# EcobitNRF9160_EV3.net
KiCad netlist of a schematic drawn in EAGLE
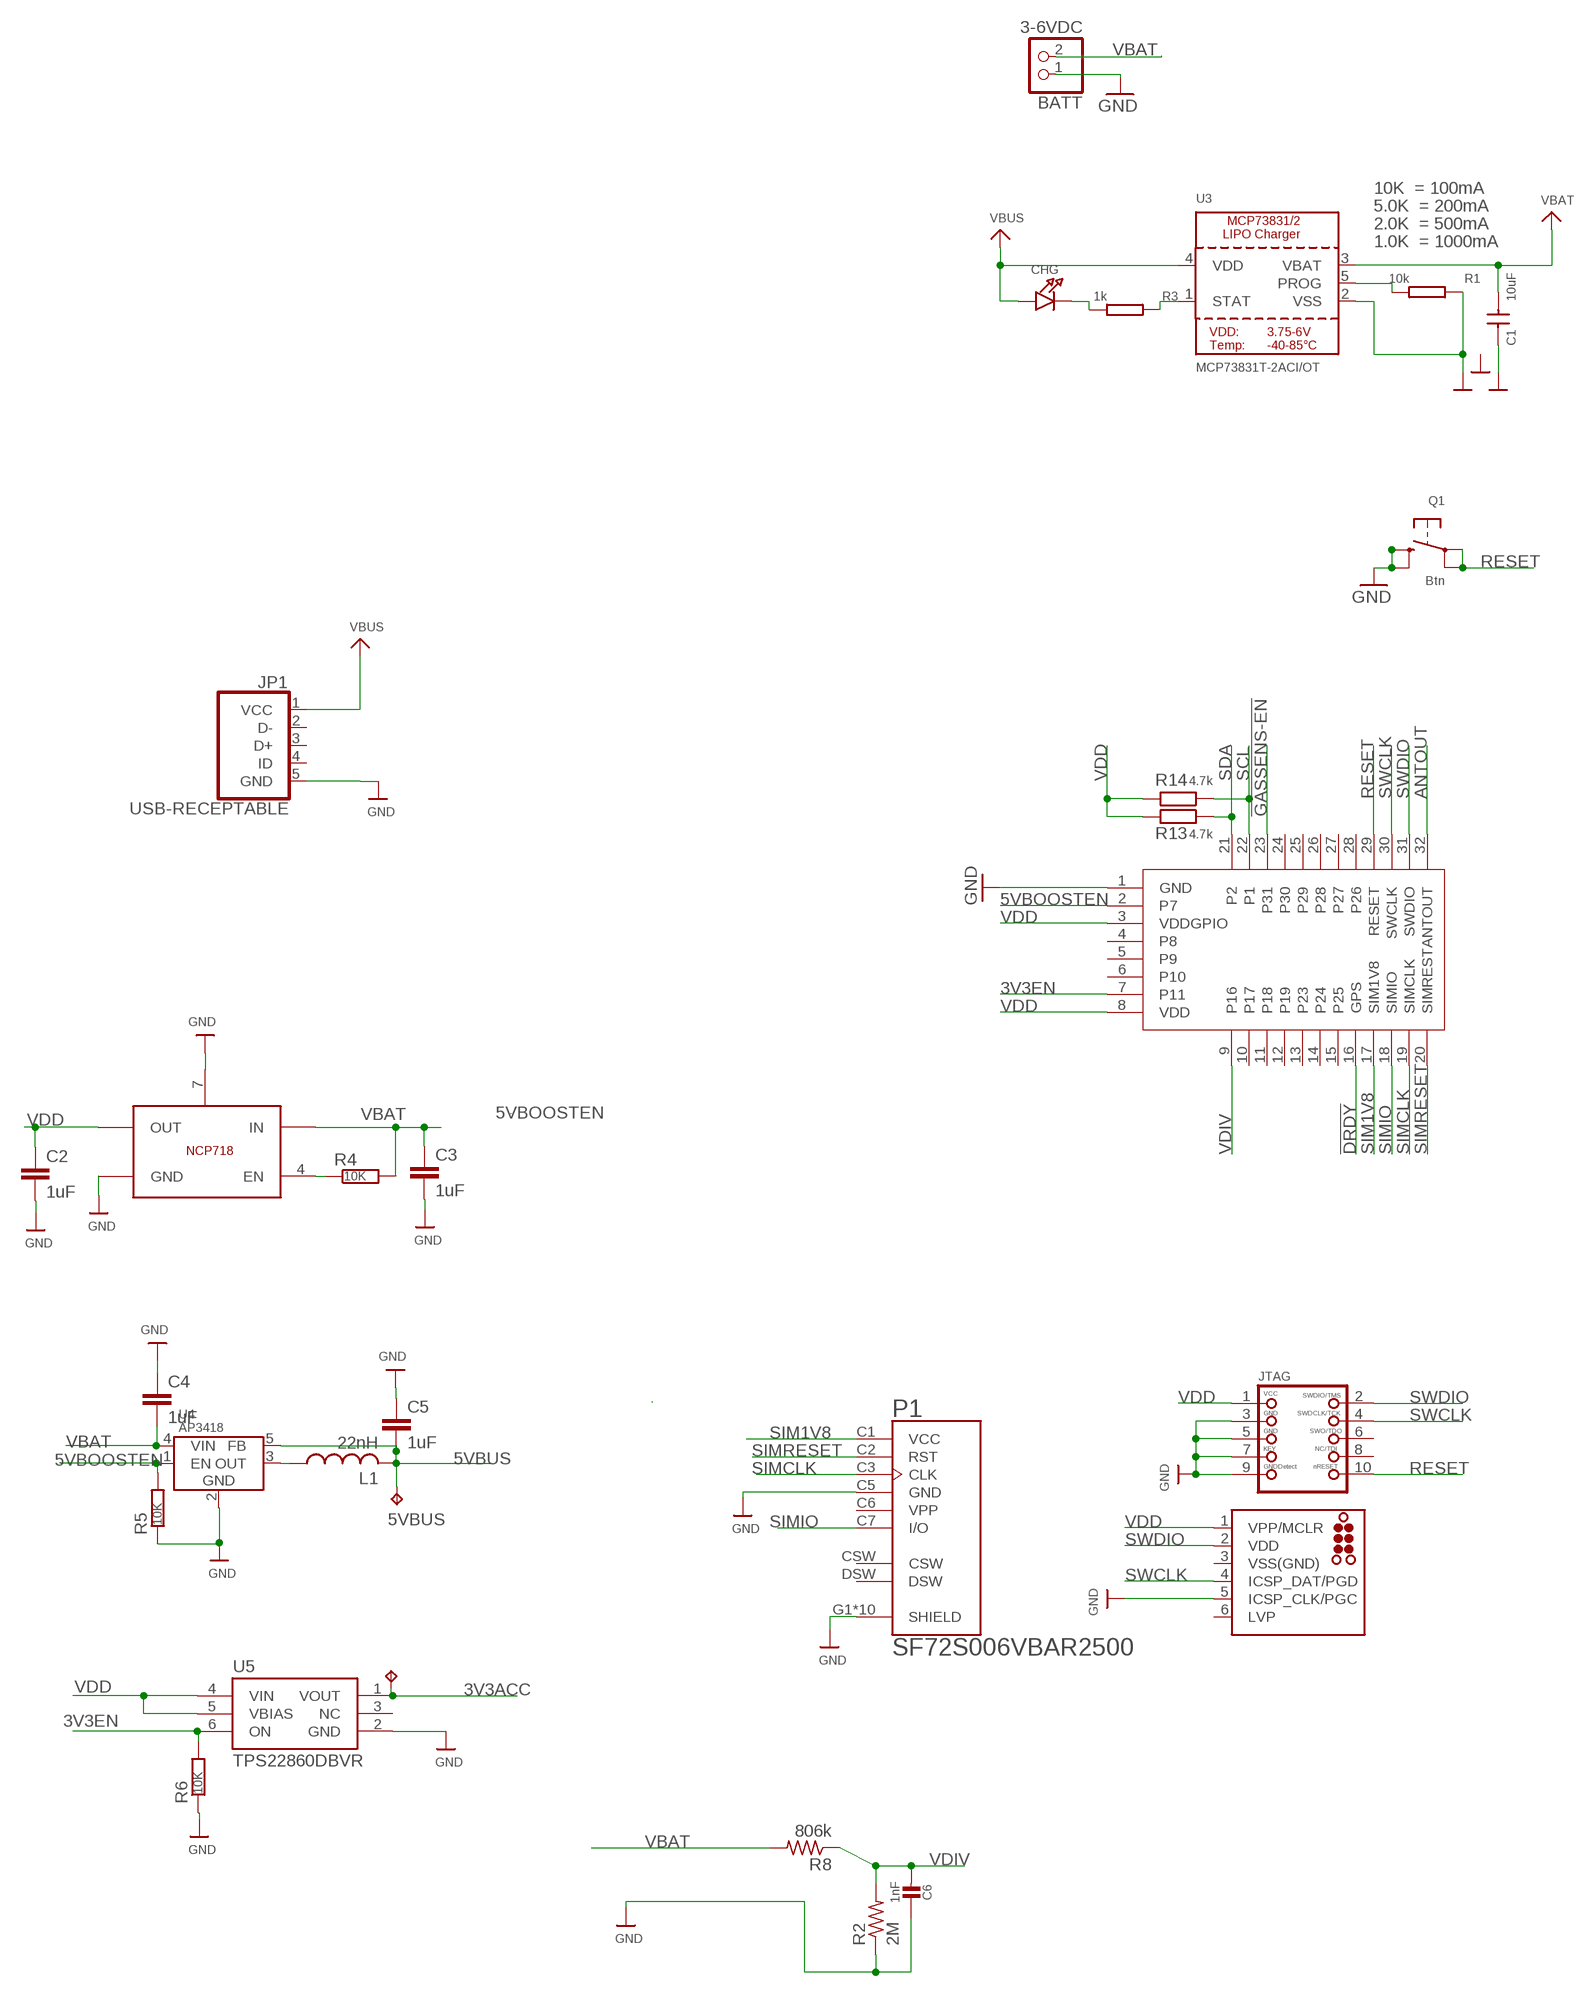
[diagram p0: schematic, sheet 1, part 1 of 2]
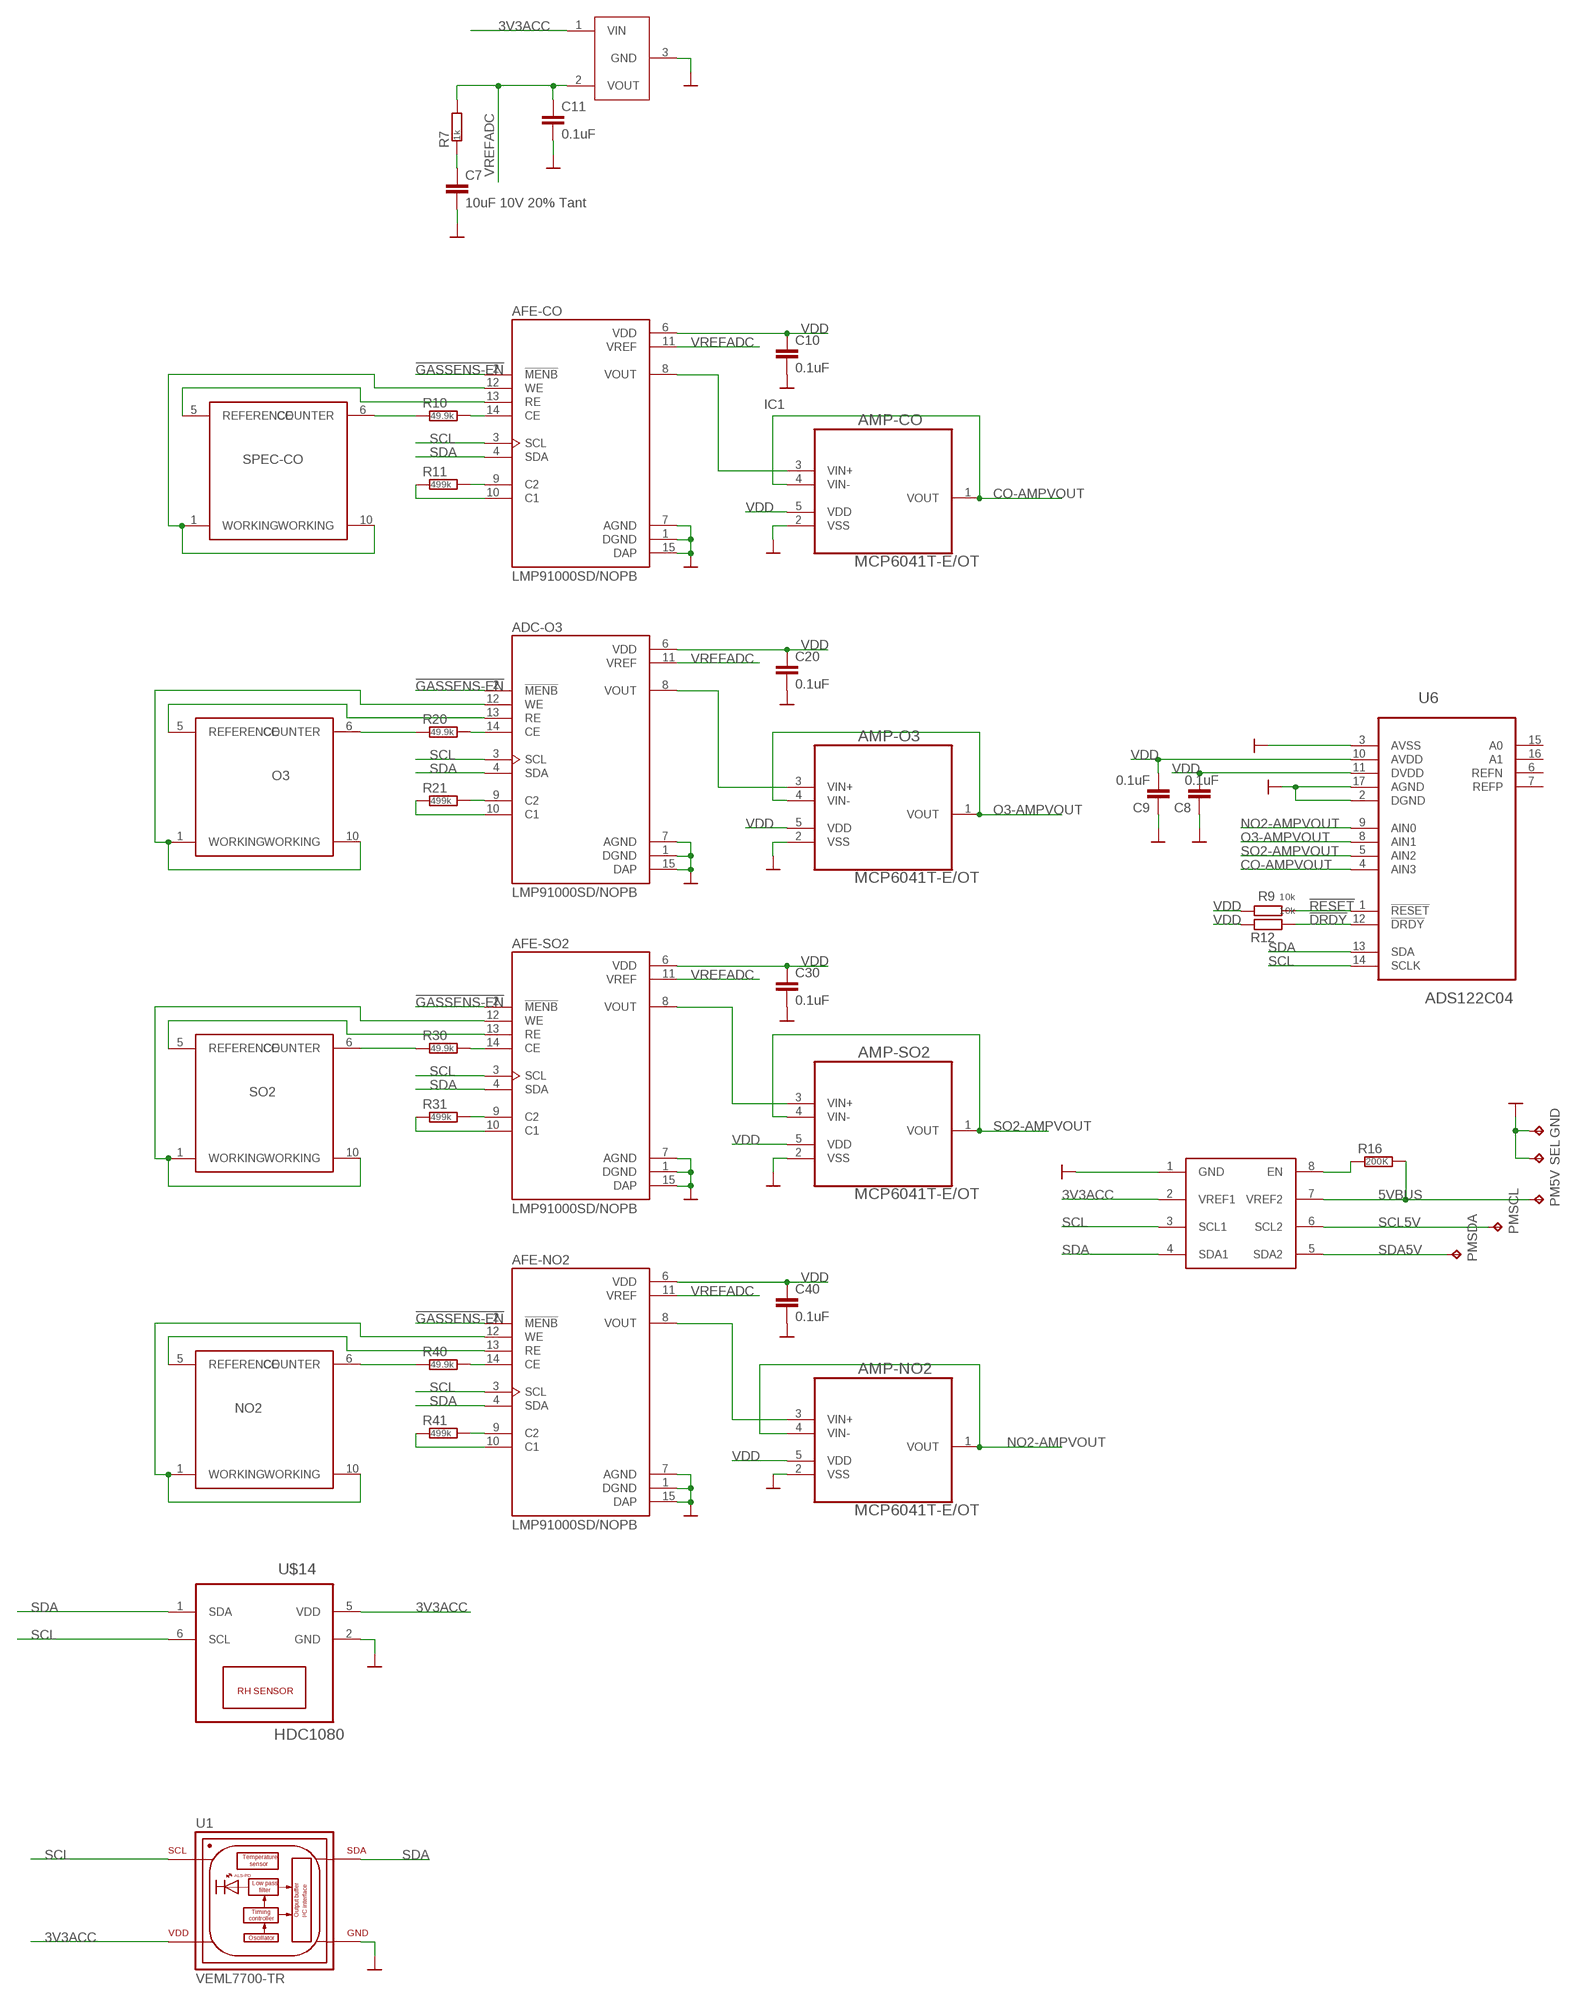
[diagram p1: schematic, sheet 1, part 2 of 2]

(export (version "E")
  (design (tool "Eeschema 10.0.6"))
  (components
    (comp (ref "5VBUS")
      (value "TPTP15R")
      (footprint "eagle-import:TP15R")
      (libsource (lib "eagle-import") (part "TPTP15R"))
    )
    (comp (ref "5VBUS1")
      (value "TPTP15R")
      (footprint "eagle-import:TP15R")
      (libsource (lib "eagle-import") (part "TPTP15R"))
    )
    (comp (ref "ADC-O3")
      (value "LMP91000SD/NOPB")
      (footprint "eagle-import:SON50P400X400X80-15N")
      (fields (field (name "MF") "Texas Instruments"))
      (libsource (lib "eagle-import") (part "LMP91000SD/NOPB"))
    )
    (comp (ref "AFE-CO")
      (value "LMP91000SD/NOPB")
      (footprint "eagle-import:SON50P400X400X80-15N")
      (fields (field (name "MF") "Texas Instruments"))
      (libsource (lib "eagle-import") (part "LMP91000SD/NOPB"))
    )
    (comp (ref "AFE-NO2")
      (value "LMP91000SD/NOPB")
      (footprint "eagle-import:SON50P400X400X80-15N")
      (fields (field (name "MF") "Texas Instruments"))
      (libsource (lib "eagle-import") (part "LMP91000SD/NOPB"))
    )
    (comp (ref "AFE-SO2")
      (value "LMP91000SD/NOPB")
      (footprint "eagle-import:SON50P400X400X80-15N")
      (fields (field (name "MF") "Texas Instruments"))
      (libsource (lib "eagle-import") (part "LMP91000SD/NOPB"))
    )
    (comp (ref "AMP-CO")
      (value "MCP6041T-E/OT")
      (footprint "eagle-import:SOT95P320X145-5N")
      (fields (field (name "MF") "Microchip"))
      (libsource (lib "eagle-import") (part "MCP6041T-E/OT"))
    )
    (comp (ref "AMP-NO2")
      (value "MCP6041T-E/OT")
      (footprint "eagle-import:SOT95P320X145-5N")
      (fields (field (name "MF") "Microchip"))
      (libsource (lib "eagle-import") (part "MCP6041T-E/OT"))
    )
    (comp (ref "AMP-O3")
      (value "MCP6041T-E/OT")
      (footprint "eagle-import:SOT95P320X145-5N")
      (fields (field (name "MF") "Microchip"))
      (libsource (lib "eagle-import") (part "MCP6041T-E/OT"))
    )
    (comp (ref "AMP-SO2")
      (value "MCP6041T-E/OT")
      (footprint "eagle-import:SOT95P320X145-5N")
      (fields (field (name "MF") "Microchip"))
      (libsource (lib "eagle-import") (part "MCP6041T-E/OT"))
    )
    (comp (ref "BATT")
      (value "3-6VDC")
      (footprint "eagle-import:JSTPH2")
      (libsource (lib "eagle-import") (part "CON_JST_PH_2PIN"))
    )
    (comp (ref "C1")
      (value "10uF")
      (footprint "eagle-import:C-0402")
      (libsource (lib "eagle-import") (part "CAP0402"))
    )
    (comp (ref "C2")
      (value "1uF")
      (footprint "eagle-import:RESC0402_N")
      (libsource (lib "eagle-import") (part "CAPACITOR_0402_N"))
    )
    (comp (ref "C3")
      (value "1uF")
      (footprint "eagle-import:RESC0402_N")
      (libsource (lib "eagle-import") (part "CAPACITOR_0402_N"))
    )
    (comp (ref "C4")
      (value "1uF")
      (footprint "eagle-import:RESC0402_N")
      (libsource (lib "eagle-import") (part "CAPACITOR_0402_N"))
    )
    (comp (ref "C5")
      (value "1uF")
      (footprint "eagle-import:RESC0402_N")
      (libsource (lib "eagle-import") (part "CAPACITOR_0402_N"))
    )
    (comp (ref "C6")
      (value "1nF")
      (footprint "eagle-import:0603-NO")
      (libsource (lib "eagle-import") (part "CAP_CERAMIC0603_NO"))
    )
    (comp (ref "C7")
      (value "10uF 10V 20% Tant")
      (footprint "eagle-import:RESC0805_N")
      (libsource (lib "eagle-import") (part "CAPACITOR_0805_N"))
    )
    (comp (ref "C8")
      (value "0.1uF")
      (footprint "eagle-import:RESC0603_N")
      (libsource (lib "eagle-import") (part "CAPACITOR_0603_N"))
    )
    (comp (ref "C9")
      (value "0.1uF")
      (footprint "eagle-import:RESC0603_N")
      (libsource (lib "eagle-import") (part "CAPACITOR_0603_N"))
    )
    (comp (ref "C10")
      (value "0.1uF")
      (footprint "eagle-import:RESC0603_N")
      (libsource (lib "eagle-import") (part "CAPACITOR_0603_N"))
    )
    (comp (ref "C11")
      (value "0.1uF")
      (footprint "eagle-import:RESC0603_N")
      (libsource (lib "eagle-import") (part "CAPACITOR_0603_N"))
    )
    (comp (ref "C20")
      (value "0.1uF")
      (footprint "eagle-import:RESC0603_N")
      (libsource (lib "eagle-import") (part "CAPACITOR_0603_N"))
    )
    (comp (ref "C30")
      (value "0.1uF")
      (footprint "eagle-import:RESC0603_N")
      (libsource (lib "eagle-import") (part "CAPACITOR_0603_N"))
    )
    (comp (ref "C40")
      (value "0.1uF")
      (footprint "eagle-import:RESC0603_N")
      (libsource (lib "eagle-import") (part "CAPACITOR_0603_N"))
    )
    (comp (ref "CHG")
      (value "LED0805_NOOUTLINE")
      (footprint "eagle-import:CHIPLED_0805_NOOUTLINE")
      (libsource (lib "eagle-import") (part "LED0805_NOOUTLINE"))
    )
    (comp (ref "GND")
      (value "TPTP15R")
      (footprint "eagle-import:TP15R")
      (libsource (lib "eagle-import") (part "TPTP15R"))
    )
    (comp (ref "IC1")
      (value "ISL60002DIH320Z-TK")
      (footprint "eagle-import:SOT-23-3")
      (libsource (lib "eagle-import") (part "ISL60002DIH320Z-TK"))
    )
    (comp (ref "J2")
      (value "TC2030-MCP-NL")
      (footprint "eagle-import:TC2030-MCP-NL")
      (libsource (lib "eagle-import") (part "TC2030-MCP-NL"))
    )
    (comp (ref "JP1")
      (value "USB-RECEPTABLE")
      (footprint "eagle-import:FCI-10103594-0001LF")
      (libsource (lib "eagle-import") (part "USB-RECEPTABLE"))
    )
    (comp (ref "JTAG")
      (value "JTAG-CORTEXM3")
      (footprint "eagle-import:2X05_1.27MM_SMT")
      (libsource (lib "eagle-import") (part "JTAG-CORTEXM3"))
    )
    (comp (ref "L1")
      (value "22nH")
      (footprint "eagle-import:RESC0603_N")
      (libsource (lib "eagle-import") (part "INDUCTOR_0603_N"))
    )
    (comp (ref "P1")
      (value "SF72S006VBAR2500")
      (footprint "eagle-import:JAE_SF72S006VBAR2500")
      (fields (field (name "MF") "JAE Electronics"))
      (libsource (lib "eagle-import") (part "SF72S006VBAR2500"))
    )
    (comp (ref "PM5V")
      (value "TPTP15R")
      (footprint "eagle-import:TP15R")
      (libsource (lib "eagle-import") (part "TPTP15R"))
    )
    (comp (ref "PMSCL")
      (value "TPTP15R")
      (footprint "eagle-import:TP15R")
      (libsource (lib "eagle-import") (part "TPTP15R"))
    )
    (comp (ref "PMSDA")
      (value "TPTP15R")
      (footprint "eagle-import:TP15R")
      (libsource (lib "eagle-import") (part "TPTP15R"))
    )
    (comp (ref "Q1")
      (value "Btn")
      (footprint "eagle-import:BTN_KMR2_4.6X2.8")
      (libsource (lib "eagle-import") (part "SWITCH_TACT_SMT4.6X2.8"))
    )
    (comp (ref "R1")
      (value "10k")
      (footprint "eagle-import:R0402")
      (libsource (lib "eagle-import") (part "RESR0402"))
    )
    (comp (ref "R2")
      (value "2M")
      (footprint "eagle-import:R0603")
      (libsource (lib "eagle-import") (part "R-US_R0603"))
    )
    (comp (ref "R3")
      (value "1k")
      (footprint "eagle-import:R0402")
      (libsource (lib "eagle-import") (part "RESR0402"))
    )
    (comp (ref "R4")
      (value "10K")
      (footprint "eagle-import:RESC0402_N")
      (libsource (lib "eagle-import") (part "RESISTOR_0402_N"))
    )
    (comp (ref "R5")
      (value "10K")
      (footprint "eagle-import:RESC0402_N")
      (libsource (lib "eagle-import") (part "RESISTOR_0402_N"))
    )
    (comp (ref "R6")
      (value "10K")
      (footprint "eagle-import:RESC0402_N")
      (libsource (lib "eagle-import") (part "RESISTOR_0402_N"))
    )
    (comp (ref "R7")
      (value "1k")
      (footprint "eagle-import:RESC0603_N")
      (libsource (lib "eagle-import") (part "RESISTOR_0603_N"))
    )
    (comp (ref "R8")
      (value "806k")
      (footprint "eagle-import:R0603")
      (libsource (lib "eagle-import") (part "R-US_R0603"))
    )
    (comp (ref "R9")
      (value "10k")
      (footprint "eagle-import:RESC0603_N")
      (libsource (lib "eagle-import") (part "RESISTOR_0603_N"))
    )
    (comp (ref "R10")
      (value "49.9k")
      (footprint "eagle-import:RESC0603_N")
      (libsource (lib "eagle-import") (part "RESISTOR_0603_N"))
    )
    (comp (ref "R11")
      (value "499k")
      (footprint "eagle-import:RESC0603_N")
      (libsource (lib "eagle-import") (part "RESISTOR_0603_N"))
    )
    (comp (ref "R12")
      (value "10k")
      (footprint "eagle-import:RESC0603_N")
      (libsource (lib "eagle-import") (part "RESISTOR_0603_N"))
    )
    (comp (ref "R13")
      (value "4.7k")
      (footprint "eagle-import:RESC0603_N")
      (libsource (lib "eagle-import") (part "RESISTOR_0603_N"))
    )
    (comp (ref "R14")
      (value "4.7k")
      (footprint "eagle-import:RESC0603_N")
      (libsource (lib "eagle-import") (part "RESISTOR_0603_N"))
    )
    (comp (ref "R16")
      (value "200K")
      (footprint "eagle-import:RESC0402_N")
      (libsource (lib "eagle-import") (part "RESISTOR_0402_N"))
    )
    (comp (ref "R20")
      (value "49.9k")
      (footprint "eagle-import:RESC0603_N")
      (libsource (lib "eagle-import") (part "RESISTOR_0603_N"))
    )
    (comp (ref "R21")
      (value "499k")
      (footprint "eagle-import:RESC0603_N")
      (libsource (lib "eagle-import") (part "RESISTOR_0603_N"))
    )
    (comp (ref "R30")
      (value "49.9k")
      (footprint "eagle-import:RESC0603_N")
      (libsource (lib "eagle-import") (part "RESISTOR_0603_N"))
    )
    (comp (ref "R31")
      (value "499k")
      (footprint "eagle-import:RESC0603_N")
      (libsource (lib "eagle-import") (part "RESISTOR_0603_N"))
    )
    (comp (ref "R40")
      (value "49.9k")
      (footprint "eagle-import:RESC0603_N")
      (libsource (lib "eagle-import") (part "RESISTOR_0603_N"))
    )
    (comp (ref "R41")
      (value "499k")
      (footprint "eagle-import:RESC0603_N")
      (libsource (lib "eagle-import") (part "RESISTOR_0603_N"))
    )
    (comp (ref "SEL")
      (value "TPTP15R")
      (footprint "eagle-import:TP15R")
      (libsource (lib "eagle-import") (part "TPTP15R"))
    )
    (comp (ref "SENS-CO")
      (value "SPECSENSOR")
      (footprint "eagle-import:SPECSENSOR")
      (libsource (lib "eagle-import") (part "SPECSENSOR"))
    )
    (comp (ref "SENS-NO2")
      (value "SPECSENSOR")
      (footprint "eagle-import:SPECSENSOR")
      (libsource (lib "eagle-import") (part "SPECSENSOR"))
    )
    (comp (ref "SENS-O3")
      (value "SPECSENSOR")
      (footprint "eagle-import:SPECSENSOR")
      (libsource (lib "eagle-import") (part "SPECSENSOR"))
    )
    (comp (ref "SENS-SO2")
      (value "SPECSENSOR")
      (footprint "eagle-import:SPECSENSOR")
      (libsource (lib "eagle-import") (part "SPECSENSOR"))
    )
    (comp (ref "U$14")
      (value "HDC1080")
      (footprint "eagle-import:TI-S-PWSON-N6")
      (libsource (lib "eagle-import") (part "HDC1080"))
    )
    (comp (ref "U$35")
      (value "NRF9160MODULE")
      (footprint "eagle-import:NRF9160CASTALLATEDMODULE")
      (libsource (lib "eagle-import") (part "NRF9160MODULE"))
    )
    (comp (ref "U1")
      (value "VEML7700-TR")
      (footprint "eagle-import:XDCR_VEML7700-TR")
      (fields (field (name "DIGI-KEY_PART_NUMBER") "VEML7700CT-ND") (field (name "MF") "Vishay"))
      (libsource (lib "eagle-import") (part "VEML7700-TR"))
    )
    (comp (ref "U2")
      (value "NCP718")
      (footprint "eagle-import:NCP718-WDFN6")
      (libsource (lib "eagle-import") (part "NCP718"))
    )
    (comp (ref "U3")
      (value "MCP73831T-2ACI/OT")
      (footprint "eagle-import:SOT23-5")
      (libsource (lib "eagle-import") (part "MCP73831/2"))
    )
    (comp (ref "U4")
      (value "AP3418")
      (footprint "eagle-import:SOT25")
      (libsource (lib "eagle-import") (part "AP3418"))
    )
    (comp (ref "U5")
      (value "TPS22860DBVR")
      (footprint "eagle-import:R-PDSO-G6")
      (libsource (lib "eagle-import") (part "TPS22860DBVR"))
    )
    (comp (ref "U6")
      (value "ADS122C04")
      (footprint "eagle-import:QFN50P300X300X80-16N")
      (fields (field (name "MF") "Texas Instruments") (field (name "MP") "ADS7924IRTER"))
      (libsource (lib "eagle-import") (part "ADS122C04"))
    )
    (comp (ref "U7")
      (value "PCA9306")
      (footprint "eagle-import:PSON35P135X100X50-8N")
      (libsource (lib "eagle-import") (part "PCA9306"))
    )
  )
  (nets
    (net (code "1") (name "/3V3ACC") (class "Default")
      (node (ref "5VBUS1") (pin "TP") (pinfunction "TP_TP") (pintype "input"))
      (node (ref "IC1") (pin "1") (pinfunction "VIN_1") (pintype "power_in"))
      (node (ref "U$14") (pin "5") (pinfunction "VDD_5") (pintype "output"))
      (node (ref "U1") (pin "2") (pinfunction "VDD_2") (pintype "power_in"))
      (node (ref "U5") (pin "1") (pinfunction "VOUT_1") (pintype "power_in"))
      (node (ref "U7") (pin "2") (pinfunction "VREF1_2") (pintype "bidirectional"))
    )
    (net (code "2") (name "/3V3EN") (class "Default")
      (node (ref "R6") (pin "2") (pinfunction "2_2") (pintype "passive"))
      (node (ref "U$35") (pin "7") (pinfunction "P11_7") (pintype "bidirectional"))
      (node (ref "U5") (pin "6") (pinfunction "ON_6") (pintype "input"))
    )
    (net (code "3") (name "/5VBOOSTEN") (class "Default")
      (node (ref "R5") (pin "2") (pinfunction "2_2") (pintype "passive"))
      (node (ref "U$35") (pin "2") (pinfunction "P7_2") (pintype "bidirectional"))
      (node (ref "U4") (pin "1") (pinfunction "EN_1") (pintype "bidirectional"))
    )
    (net (code "4") (name "/5VBUS") (class "Default")
      (node (ref "5VBUS") (pin "TP") (pinfunction "TP_TP") (pintype "input"))
      (node (ref "C5") (pin "2") (pinfunction "2_2") (pintype "passive"))
      (node (ref "L1") (pin "2") (pinfunction "2_2") (pintype "passive"))
      (node (ref "PM5V") (pin "TP") (pinfunction "TP_TP") (pintype "input"))
      (node (ref "R16") (pin "2") (pinfunction "2_2") (pintype "passive"))
      (node (ref "U4") (pin "5") (pinfunction "FB_5") (pintype "bidirectional"))
      (node (ref "U7") (pin "7") (pinfunction "VREF2_7") (pintype "bidirectional"))
    )
    (net (code "5") (name "/ANTOUT") (class "Default")
      (node (ref "U$35") (pin "32") (pinfunction "ANTOUT_32") (pintype "bidirectional"))
    )
    (net (code "6") (name "/CO-AMPVOUT") (class "Default")
      (node (ref "AMP-CO") (pin "1") (pinfunction "VOUT_1") (pintype "output"))
      (node (ref "AMP-CO") (pin "4") (pinfunction "VIN-_4") (pintype "input"))
      (node (ref "U6") (pin "4") (pinfunction "AIN3_4") (pintype "input"))
    )
    (net (code "9") (name "/NO2-AMPVOUT") (class "Default")
      (node (ref "AMP-NO2") (pin "1") (pinfunction "VOUT_1") (pintype "output"))
      (node (ref "AMP-NO2") (pin "4") (pinfunction "VIN-_4") (pintype "input"))
      (node (ref "U6") (pin "9") (pinfunction "AIN0_9") (pintype "input"))
    )
    (net (code "11") (name "/O3-AMPVOUT") (class "Default")
      (node (ref "AMP-O3") (pin "1") (pinfunction "VOUT_1") (pintype "output"))
      (node (ref "AMP-O3") (pin "4") (pinfunction "VIN-_4") (pintype "input"))
      (node (ref "U6") (pin "8") (pinfunction "AIN1_8") (pintype "input"))
    )
    (net (code "12") (name "/RESET") (class "Default")
      (node (ref "JTAG") (pin "10") (pinfunction "10_10") (pintype "passive"))
      (node (ref "Q1") (pin "A") (pinfunction "P_A") (pintype "passive"))
      (node (ref "Q1") (pin "A'") (pinfunction "P1_A'") (pintype "passive"))
      (node (ref "U$35") (pin "29") (pinfunction "RESET_29") (pintype "bidirectional"))
    )
    (net (code "13") (name "/SCL") (class "Default")
      (node (ref "ADC-O3") (pin "3") (pinfunction "SCL_3") (pintype "input"))
      (node (ref "AFE-CO") (pin "3") (pinfunction "SCL_3") (pintype "input"))
      (node (ref "AFE-NO2") (pin "3") (pinfunction "SCL_3") (pintype "input"))
      (node (ref "AFE-SO2") (pin "3") (pinfunction "SCL_3") (pintype "input"))
      (node (ref "R14") (pin "1") (pinfunction "1_1") (pintype "passive"))
      (node (ref "U$14") (pin "6") (pinfunction "SCL_6") (pintype "passive"))
      (node (ref "U$35") (pin "22") (pinfunction "P1_22") (pintype "bidirectional"))
      (node (ref "U1") (pin "1") (pinfunction "SCL_1") (pintype "input"))
      (node (ref "U6") (pin "14") (pinfunction "SCLK_14") (pintype "input"))
      (node (ref "U7") (pin "3") (pinfunction "SCL1_3") (pintype "bidirectional"))
    )
    (net (code "14") (name "/SCL5V") (class "Default")
      (node (ref "PMSCL") (pin "TP") (pinfunction "TP_TP") (pintype "input"))
      (node (ref "U7") (pin "6") (pinfunction "SCL2_6") (pintype "bidirectional"))
    )
    (net (code "15") (name "/SDA") (class "Default")
      (node (ref "ADC-O3") (pin "4") (pinfunction "SDA_4") (pintype "bidirectional"))
      (node (ref "AFE-CO") (pin "4") (pinfunction "SDA_4") (pintype "bidirectional"))
      (node (ref "AFE-NO2") (pin "4") (pinfunction "SDA_4") (pintype "bidirectional"))
      (node (ref "AFE-SO2") (pin "4") (pinfunction "SDA_4") (pintype "bidirectional"))
      (node (ref "R13") (pin "1") (pinfunction "1_1") (pintype "passive"))
      (node (ref "U$14") (pin "1") (pinfunction "SDA_1") (pintype "power_in"))
      (node (ref "U$35") (pin "21") (pinfunction "P2_21") (pintype "bidirectional"))
      (node (ref "U1") (pin "4") (pinfunction "SDA_4") (pintype "bidirectional"))
      (node (ref "U6") (pin "13") (pinfunction "SDA_13") (pintype "input"))
      (node (ref "U7") (pin "4") (pinfunction "SDA1_4") (pintype "bidirectional"))
    )
    (net (code "16") (name "/SDA5V") (class "Default")
      (node (ref "PMSDA") (pin "TP") (pinfunction "TP_TP") (pintype "input"))
      (node (ref "U7") (pin "5") (pinfunction "SDA2_5") (pintype "bidirectional"))
    )
    (net (code "17") (name "/SIM1V8") (class "Default")
      (node (ref "P1") (pin "C1") (pinfunction "VCC_C1") (pintype "power_in"))
      (node (ref "U$35") (pin "17") (pinfunction "SIM1V8_17") (pintype "bidirectional"))
    )
    (net (code "18") (name "/SIMCLK") (class "Default")
      (node (ref "P1") (pin "C3") (pinfunction "CLK_C3") (pintype "bidirectional"))
      (node (ref "U$35") (pin "19") (pinfunction "SIMCLK_19") (pintype "bidirectional"))
    )
    (net (code "19") (name "/SIMIO") (class "Default")
      (node (ref "P1") (pin "C7") (pinfunction "I/O_C7") (pintype "bidirectional"))
      (node (ref "U$35") (pin "18") (pinfunction "SIMIO_18") (pintype "bidirectional"))
    )
    (net (code "20") (name "/SIMRESET") (class "Default")
      (node (ref "P1") (pin "C2") (pinfunction "RST_C2") (pintype "bidirectional"))
      (node (ref "U$35") (pin "20") (pinfunction "SIMREST_20") (pintype "bidirectional"))
    )
    (net (code "22") (name "/SO2-AMPVOUT") (class "Default")
      (node (ref "AMP-SO2") (pin "1") (pinfunction "VOUT_1") (pintype "output"))
      (node (ref "AMP-SO2") (pin "4") (pinfunction "VIN-_4") (pintype "input"))
      (node (ref "U6") (pin "5") (pinfunction "AIN2_5") (pintype "input"))
    )
    (net (code "24") (name "/SWCLK") (class "Default")
      (node (ref "J2") (pin "4") (pinfunction "ICSP_DAT/PGD_4") (pintype "bidirectional"))
      (node (ref "JTAG") (pin "4") (pinfunction "4_4") (pintype "passive"))
      (node (ref "U$35") (pin "30") (pinfunction "SWCLK_30") (pintype "bidirectional"))
    )
    (net (code "25") (name "/SWDIO") (class "Default")
      (node (ref "J2") (pin "2") (pinfunction "VDD_2") (pintype "power_in"))
      (node (ref "JTAG") (pin "2") (pinfunction "2_2") (pintype "passive"))
      (node (ref "U$35") (pin "31") (pinfunction "SWDIO_31") (pintype "bidirectional"))
    )
    (net (code "26") (name "/VDD") (class "Default")
      (node (ref "ADC-O3") (pin "6") (pinfunction "VDD_6") (pintype "power_in"))
      (node (ref "AFE-CO") (pin "6") (pinfunction "VDD_6") (pintype "power_in"))
      (node (ref "AFE-NO2") (pin "6") (pinfunction "VDD_6") (pintype "power_in"))
      (node (ref "AFE-SO2") (pin "6") (pinfunction "VDD_6") (pintype "power_in"))
      (node (ref "AMP-CO") (pin "5") (pinfunction "VDD_5") (pintype "power_in"))
      (node (ref "AMP-NO2") (pin "5") (pinfunction "VDD_5") (pintype "power_in"))
      (node (ref "AMP-O3") (pin "5") (pinfunction "VDD_5") (pintype "power_in"))
      (node (ref "AMP-SO2") (pin "5") (pinfunction "VDD_5") (pintype "power_in"))
      (node (ref "C10") (pin "1") (pinfunction "1_1") (pintype "passive"))
      (node (ref "C2") (pin "1") (pinfunction "1_1") (pintype "passive"))
      (node (ref "C20") (pin "1") (pinfunction "1_1") (pintype "passive"))
      (node (ref "C30") (pin "1") (pinfunction "1_1") (pintype "passive"))
      (node (ref "C40") (pin "1") (pinfunction "1_1") (pintype "passive"))
      (node (ref "C8") (pin "2") (pinfunction "2_2") (pintype "passive"))
      (node (ref "C9") (pin "2") (pinfunction "2_2") (pintype "passive"))
      (node (ref "J2") (pin "1") (pinfunction "VPP/MCLR_1") (pintype "passive"))
      (node (ref "JTAG") (pin "1") (pinfunction "1_1") (pintype "passive"))
      (node (ref "R12") (pin "2") (pinfunction "2_2") (pintype "passive"))
      (node (ref "R13") (pin "2") (pinfunction "2_2") (pintype "passive"))
      (node (ref "R14") (pin "2") (pinfunction "2_2") (pintype "passive"))
      (node (ref "R9") (pin "2") (pinfunction "2_2") (pintype "passive"))
      (node (ref "U$35") (pin "3") (pinfunction "VDDGPIO_3") (pintype "bidirectional"))
      (node (ref "U$35") (pin "8") (pinfunction "VDD_8") (pintype "bidirectional"))
      (node (ref "U2") (pin "1") (pinfunction "OUT_1") (pintype "power_in"))
      (node (ref "U5") (pin "4") (pinfunction "VIN_4") (pintype "power_in"))
      (node (ref "U5") (pin "5") (pinfunction "VBIAS_5") (pintype "power_in"))
      (node (ref "U6") (pin "10") (pinfunction "AVDD_10") (pintype "input"))
      (node (ref "U6") (pin "11") (pinfunction "DVDD_11") (pintype "power_in"))
    )
    (net (code "27") (name "/VDIV") (class "Default")
      (node (ref "C6") (pin "2") (pinfunction "2_2") (pintype "passive"))
      (node (ref "R2") (pin "2") (pinfunction "2_2") (pintype "passive"))
      (node (ref "R8") (pin "1") (pinfunction "1_1") (pintype "passive"))
      (node (ref "U$35") (pin "9") (pinfunction "P16_9") (pintype "bidirectional"))
    )
    (net (code "28") (name "/VPP") (class "Default")
      (node (ref "P1") (pin "C6") (pinfunction "VPP_C6") (pintype "power_in"))
    )
    (net (code "29") (name "/VREFADC") (class "Default")
      (node (ref "ADC-O3") (pin "11") (pinfunction "VREF_11") (pintype "power_in"))
      (node (ref "AFE-CO") (pin "11") (pinfunction "VREF_11") (pintype "power_in"))
      (node (ref "AFE-NO2") (pin "11") (pinfunction "VREF_11") (pintype "power_in"))
      (node (ref "AFE-SO2") (pin "11") (pinfunction "VREF_11") (pintype "power_in"))
      (node (ref "C11") (pin "1") (pinfunction "1_1") (pintype "passive"))
      (node (ref "IC1") (pin "2") (pinfunction "VOUT_2") (pintype "power_in"))
      (node (ref "R7") (pin "2") (pinfunction "2_2") (pintype "passive"))
    )
    (net (code "30") (name "/VSS(GND)") (class "Default")
      (node (ref "J2") (pin "3") (pinfunction "VSS(GND)_3") (pintype "power_in"))
    )
    (net (code "31") (name "/~{DRDY}") (class "Default")
      (node (ref "R12") (pin "1") (pinfunction "1_1") (pintype "passive"))
      (node (ref "U$35") (pin "16") (pinfunction "GPS_16") (pintype "bidirectional"))
      (node (ref "U6") (pin "12") (pinfunction "~{DRDY}_12") (pintype "passive"))
    )
    (net (code "32") (name "/~{GASSENS-EN}") (class "Default")
      (node (ref "ADC-O3") (pin "2") (pinfunction "~{MENB}_2") (pintype "input"))
      (node (ref "AFE-CO") (pin "2") (pinfunction "~{MENB}_2") (pintype "input"))
      (node (ref "AFE-NO2") (pin "2") (pinfunction "~{MENB}_2") (pintype "input"))
      (node (ref "AFE-SO2") (pin "2") (pinfunction "~{MENB}_2") (pintype "input"))
      (node (ref "U$35") (pin "23") (pinfunction "P31_23") (pintype "bidirectional"))
    )
    (net (code "33") (name "/~{RESET}") (class "Default")
      (node (ref "R9") (pin "1") (pinfunction "1_1") (pintype "passive"))
      (node (ref "U6") (pin "1") (pinfunction "~{RESET}_1") (pintype "input"))
    )
    (net (code "34") (name "GND") (class "Default")
      (node (ref "ADC-O3") (pin "1") (pinfunction "DGND_1") (pintype "power_in"))
      (node (ref "ADC-O3") (pin "15") (pinfunction "DAP_15") (pintype "power_in"))
      (node (ref "ADC-O3") (pin "7") (pinfunction "AGND_7") (pintype "power_in"))
      (node (ref "AFE-CO") (pin "1") (pinfunction "DGND_1") (pintype "power_in"))
      (node (ref "AFE-CO") (pin "15") (pinfunction "DAP_15") (pintype "power_in"))
      (node (ref "AFE-CO") (pin "7") (pinfunction "AGND_7") (pintype "power_in"))
      (node (ref "AFE-NO2") (pin "1") (pinfunction "DGND_1") (pintype "power_in"))
      (node (ref "AFE-NO2") (pin "15") (pinfunction "DAP_15") (pintype "power_in"))
      (node (ref "AFE-NO2") (pin "7") (pinfunction "AGND_7") (pintype "power_in"))
      (node (ref "AFE-SO2") (pin "1") (pinfunction "DGND_1") (pintype "power_in"))
      (node (ref "AFE-SO2") (pin "15") (pinfunction "DAP_15") (pintype "power_in"))
      (node (ref "AFE-SO2") (pin "7") (pinfunction "AGND_7") (pintype "power_in"))
      (node (ref "AMP-CO") (pin "2") (pinfunction "VSS_2") (pintype "passive"))
      (node (ref "AMP-NO2") (pin "2") (pinfunction "VSS_2") (pintype "passive"))
      (node (ref "AMP-O3") (pin "2") (pinfunction "VSS_2") (pintype "passive"))
      (node (ref "AMP-SO2") (pin "2") (pinfunction "VSS_2") (pintype "passive"))
      (node (ref "BATT") (pin "1") (pinfunction "1_1") (pintype "passive"))
      (node (ref "C1") (pin "2") (pinfunction "2_2") (pintype "bidirectional"))
      (node (ref "C10") (pin "2") (pinfunction "2_2") (pintype "passive"))
      (node (ref "C11") (pin "2") (pinfunction "2_2") (pintype "passive"))
      (node (ref "C2") (pin "2") (pinfunction "2_2") (pintype "passive"))
      (node (ref "C20") (pin "2") (pinfunction "2_2") (pintype "passive"))
      (node (ref "C3") (pin "2") (pinfunction "2_2") (pintype "passive"))
      (node (ref "C30") (pin "2") (pinfunction "2_2") (pintype "passive"))
      (node (ref "C4") (pin "1") (pinfunction "1_1") (pintype "passive"))
      (node (ref "C40") (pin "2") (pinfunction "2_2") (pintype "passive"))
      (node (ref "C5") (pin "1") (pinfunction "1_1") (pintype "passive"))
      (node (ref "C6") (pin "1") (pinfunction "1_1") (pintype "passive"))
      (node (ref "C7") (pin "2") (pinfunction "2_2") (pintype "passive"))
      (node (ref "C8") (pin "1") (pinfunction "1_1") (pintype "passive"))
      (node (ref "C9") (pin "1") (pinfunction "1_1") (pintype "passive"))
      (node (ref "GND") (pin "TP") (pinfunction "TP_TP") (pintype "input"))
      (node (ref "IC1") (pin "3") (pinfunction "GND_3") (pintype "power_in"))
      (node (ref "J2") (pin "5") (pinfunction "ICSP_CLK/PGC_5") (pintype "output"))
      (node (ref "JP1") (pin "5") (pinfunction "GND_5") (pintype "bidirectional"))
      (node (ref "JTAG") (pin "3") (pinfunction "3_3") (pintype "passive"))
      (node (ref "JTAG") (pin "5") (pinfunction "5_5") (pintype "passive"))
      (node (ref "JTAG") (pin "7") (pinfunction "7_7") (pintype "passive"))
      (node (ref "JTAG") (pin "9") (pinfunction "9_9") (pintype "passive"))
      (node (ref "P1") (pin "C5") (pinfunction "GND_C5") (pintype "power_in"))
      (node (ref "P1") (pin "G1") (pinfunction "SHIELD_G1") (pintype "passive"))
      (node (ref "P1") (pin "G10") (pinfunction "SHIELD_G10") (pintype "passive"))
      (node (ref "P1") (pin "G2") (pinfunction "SHIELD_G2") (pintype "passive"))
      (node (ref "P1") (pin "G3") (pinfunction "SHIELD_G3") (pintype "passive"))
      (node (ref "P1") (pin "G4") (pinfunction "SHIELD_G4") (pintype "passive"))
      (node (ref "P1") (pin "G5") (pinfunction "SHIELD_G5") (pintype "passive"))
      (node (ref "P1") (pin "G6") (pinfunction "SHIELD_G6") (pintype "passive"))
      (node (ref "P1") (pin "G7") (pinfunction "SHIELD_G7") (pintype "passive"))
      (node (ref "P1") (pin "G8") (pinfunction "SHIELD_G8") (pintype "passive"))
      (node (ref "P1") (pin "G9") (pinfunction "SHIELD_G9") (pintype "passive"))
      (node (ref "Q1") (pin "B") (pinfunction "S_B") (pintype "passive"))
      (node (ref "Q1") (pin "B'") (pinfunction "S1_B'") (pintype "passive"))
      (node (ref "R1") (pin "1") (pinfunction "1_1") (pintype "bidirectional"))
      (node (ref "R2") (pin "1") (pinfunction "1_1") (pintype "passive"))
      (node (ref "R5") (pin "1") (pinfunction "1_1") (pintype "passive"))
      (node (ref "R6") (pin "1") (pinfunction "1_1") (pintype "passive"))
      (node (ref "SEL") (pin "TP") (pinfunction "TP_TP") (pintype "input"))
      (node (ref "U$14") (pin "2") (pinfunction "GND_2") (pintype "passive"))
      (node (ref "U$35") (pin "1") (pinfunction "GND_1") (pintype "bidirectional"))
      (node (ref "U1") (pin "3") (pinfunction "GND_3") (pintype "power_in"))
      (node (ref "U2") (pin "3") (pinfunction "GND_3") (pintype "power_in"))
      (node (ref "U2") (pin "7") (pinfunction "GND_7") (pintype "power_in"))
      (node (ref "U3") (pin "2") (pinfunction "VSS_2") (pintype "power_in"))
      (node (ref "U4") (pin "2") (pinfunction "GND_2") (pintype "bidirectional"))
      (node (ref "U5") (pin "2") (pinfunction "GND_2") (pintype "power_in"))
      (node (ref "U6") (pin "17") (pinfunction "AGND_17") (pintype "passive"))
      (node (ref "U6") (pin "2") (pinfunction "DGND_2") (pintype "passive"))
      (node (ref "U6") (pin "3") (pinfunction "AVSS_3") (pintype "power_in"))
      (node (ref "U7") (pin "1") (pinfunction "GND_1") (pintype "power_in"))
    )
    (net (code "35") (name "Net-(ADC-O3-C1)") (class "Default")
      (node (ref "ADC-O3") (pin "10") (pinfunction "C1_10") (pintype "passive"))
      (node (ref "R21") (pin "1") (pinfunction "1_1") (pintype "passive"))
    )
    (net (code "36") (name "Net-(ADC-O3-C2)") (class "Default")
      (node (ref "ADC-O3") (pin "9") (pinfunction "C2_9") (pintype "passive"))
      (node (ref "R21") (pin "2") (pinfunction "2_2") (pintype "passive"))
    )
    (net (code "37") (name "Net-(ADC-O3-CE)") (class "Default")
      (node (ref "ADC-O3") (pin "14") (pinfunction "CE_14") (pintype "input"))
      (node (ref "R20") (pin "2") (pinfunction "2_2") (pintype "passive"))
    )
    (net (code "38") (name "Net-(ADC-O3-RE)") (class "Default")
      (node (ref "ADC-O3") (pin "13") (pinfunction "RE_13") (pintype "input"))
      (node (ref "SENS-O3") (pin "5") (pinfunction "REFERENCE_5") (pintype "bidirectional"))
    )
    (net (code "39") (name "Net-(ADC-O3-VOUT)") (class "Default")
      (node (ref "ADC-O3") (pin "8") (pinfunction "VOUT_8") (pintype "output"))
      (node (ref "AMP-O3") (pin "3") (pinfunction "VIN+_3") (pintype "input"))
    )
    (net (code "40") (name "Net-(ADC-O3-WE)") (class "Default")
      (node (ref "ADC-O3") (pin "12") (pinfunction "WE_12") (pintype "input"))
      (node (ref "SENS-O3") (pin "1") (pinfunction "WORKING_1") (pintype "bidirectional"))
      (node (ref "SENS-O3") (pin "10") (pinfunction "WORKING_10") (pintype "bidirectional"))
    )
    (net (code "41") (name "Net-(AFE-CO-C1)") (class "Default")
      (node (ref "AFE-CO") (pin "10") (pinfunction "C1_10") (pintype "passive"))
      (node (ref "R11") (pin "1") (pinfunction "1_1") (pintype "passive"))
    )
    (net (code "42") (name "Net-(AFE-CO-C2)") (class "Default")
      (node (ref "AFE-CO") (pin "9") (pinfunction "C2_9") (pintype "passive"))
      (node (ref "R11") (pin "2") (pinfunction "2_2") (pintype "passive"))
    )
    (net (code "43") (name "Net-(AFE-CO-CE)") (class "Default")
      (node (ref "AFE-CO") (pin "14") (pinfunction "CE_14") (pintype "input"))
      (node (ref "R10") (pin "2") (pinfunction "2_2") (pintype "passive"))
    )
    (net (code "44") (name "Net-(AFE-CO-RE)") (class "Default")
      (node (ref "AFE-CO") (pin "13") (pinfunction "RE_13") (pintype "input"))
      (node (ref "SENS-CO") (pin "5") (pinfunction "REFERENCE_5") (pintype "bidirectional"))
    )
    (net (code "45") (name "Net-(AFE-CO-VOUT)") (class "Default")
      (node (ref "AFE-CO") (pin "8") (pinfunction "VOUT_8") (pintype "output"))
      (node (ref "AMP-CO") (pin "3") (pinfunction "VIN+_3") (pintype "input"))
    )
    (net (code "46") (name "Net-(AFE-CO-WE)") (class "Default")
      (node (ref "AFE-CO") (pin "12") (pinfunction "WE_12") (pintype "input"))
      (node (ref "SENS-CO") (pin "1") (pinfunction "WORKING_1") (pintype "bidirectional"))
      (node (ref "SENS-CO") (pin "10") (pinfunction "WORKING_10") (pintype "bidirectional"))
    )
    (net (code "47") (name "Net-(AFE-NO2-C1)") (class "Default")
      (node (ref "AFE-NO2") (pin "10") (pinfunction "C1_10") (pintype "passive"))
      (node (ref "R41") (pin "1") (pinfunction "1_1") (pintype "passive"))
    )
    (net (code "48") (name "Net-(AFE-NO2-C2)") (class "Default")
      (node (ref "AFE-NO2") (pin "9") (pinfunction "C2_9") (pintype "passive"))
      (node (ref "R41") (pin "2") (pinfunction "2_2") (pintype "passive"))
    )
    (net (code "49") (name "Net-(AFE-NO2-CE)") (class "Default")
      (node (ref "AFE-NO2") (pin "14") (pinfunction "CE_14") (pintype "input"))
      (node (ref "R40") (pin "2") (pinfunction "2_2") (pintype "passive"))
    )
    (net (code "50") (name "Net-(AFE-NO2-RE)") (class "Default")
      (node (ref "AFE-NO2") (pin "13") (pinfunction "RE_13") (pintype "input"))
      (node (ref "SENS-NO2") (pin "5") (pinfunction "REFERENCE_5") (pintype "bidirectional"))
    )
    (net (code "51") (name "Net-(AFE-NO2-VOUT)") (class "Default")
      (node (ref "AFE-NO2") (pin "8") (pinfunction "VOUT_8") (pintype "output"))
      (node (ref "AMP-NO2") (pin "3") (pinfunction "VIN+_3") (pintype "input"))
    )
    (net (code "52") (name "Net-(AFE-NO2-WE)") (class "Default")
      (node (ref "AFE-NO2") (pin "12") (pinfunction "WE_12") (pintype "input"))
      (node (ref "SENS-NO2") (pin "1") (pinfunction "WORKING_1") (pintype "bidirectional"))
      (node (ref "SENS-NO2") (pin "10") (pinfunction "WORKING_10") (pintype "bidirectional"))
    )
    (net (code "53") (name "Net-(AFE-SO2-C1)") (class "Default")
      (node (ref "AFE-SO2") (pin "10") (pinfunction "C1_10") (pintype "passive"))
      (node (ref "R31") (pin "1") (pinfunction "1_1") (pintype "passive"))
    )
    (net (code "54") (name "Net-(AFE-SO2-C2)") (class "Default")
      (node (ref "AFE-SO2") (pin "9") (pinfunction "C2_9") (pintype "passive"))
      (node (ref "R31") (pin "2") (pinfunction "2_2") (pintype "passive"))
    )
    (net (code "55") (name "Net-(AFE-SO2-CE)") (class "Default")
      (node (ref "AFE-SO2") (pin "14") (pinfunction "CE_14") (pintype "input"))
      (node (ref "R30") (pin "2") (pinfunction "2_2") (pintype "passive"))
    )
    (net (code "56") (name "Net-(AFE-SO2-RE)") (class "Default")
      (node (ref "AFE-SO2") (pin "13") (pinfunction "RE_13") (pintype "input"))
      (node (ref "SENS-SO2") (pin "5") (pinfunction "REFERENCE_5") (pintype "bidirectional"))
    )
    (net (code "57") (name "Net-(AFE-SO2-VOUT)") (class "Default")
      (node (ref "AFE-SO2") (pin "8") (pinfunction "VOUT_8") (pintype "output"))
      (node (ref "AMP-SO2") (pin "3") (pinfunction "VIN+_3") (pintype "input"))
    )
    (net (code "58") (name "Net-(AFE-SO2-WE)") (class "Default")
      (node (ref "AFE-SO2") (pin "12") (pinfunction "WE_12") (pintype "input"))
      (node (ref "SENS-SO2") (pin "1") (pinfunction "WORKING_1") (pintype "bidirectional"))
      (node (ref "SENS-SO2") (pin "10") (pinfunction "WORKING_10") (pintype "bidirectional"))
    )
    (net (code "59") (name "Net-(C7-Pad1)") (class "Default")
      (node (ref "C7") (pin "1") (pinfunction "1_1") (pintype "passive"))
      (node (ref "R7") (pin "1") (pinfunction "1_1") (pintype "passive"))
    )
    (net (code "60") (name "Net-(CHG-PadC)") (class "Default")
      (node (ref "CHG") (pin "C") (pinfunction "C_C") (pintype "passive"))
      (node (ref "R3") (pin "2") (pinfunction "2_2") (pintype "bidirectional"))
    )
    (net (code "61") (name "Net-(SENS-CO-COUNTER)") (class "Default")
      (node (ref "R10") (pin "1") (pinfunction "1_1") (pintype "passive"))
      (node (ref "SENS-CO") (pin "6") (pinfunction "COUNTER_6") (pintype "bidirectional"))
    )
    (net (code "62") (name "Net-(SENS-NO2-COUNTER)") (class "Default")
      (node (ref "R40") (pin "1") (pinfunction "1_1") (pintype "passive"))
      (node (ref "SENS-NO2") (pin "6") (pinfunction "COUNTER_6") (pintype "bidirectional"))
    )
    (net (code "63") (name "Net-(SENS-O3-COUNTER)") (class "Default")
      (node (ref "R20") (pin "1") (pinfunction "1_1") (pintype "passive"))
      (node (ref "SENS-O3") (pin "6") (pinfunction "COUNTER_6") (pintype "bidirectional"))
    )
    (net (code "64") (name "Net-(SENS-SO2-COUNTER)") (class "Default")
      (node (ref "R30") (pin "1") (pinfunction "1_1") (pintype "passive"))
      (node (ref "SENS-SO2") (pin "6") (pinfunction "COUNTER_6") (pintype "bidirectional"))
    )
    (net (code "65") (name "Net-(U2-EN)") (class "Default")
      (node (ref "R4") (pin "1") (pinfunction "1_1") (pintype "passive"))
      (node (ref "U2") (pin "4") (pinfunction "EN_4") (pintype "bidirectional"))
    )
    (net (code "66") (name "Net-(U3-PROG)") (class "Default")
      (node (ref "R1") (pin "2") (pinfunction "2_2") (pintype "bidirectional"))
      (node (ref "U3") (pin "5") (pinfunction "PROG_5") (pintype "input"))
    )
    (net (code "67") (name "Net-(U3-STAT)") (class "Default")
      (node (ref "R3") (pin "1") (pinfunction "1_1") (pintype "bidirectional"))
      (node (ref "U3") (pin "1") (pinfunction "STAT_1") (pintype "output"))
    )
    (net (code "68") (name "Net-(U4-OUT)") (class "Default")
      (node (ref "L1") (pin "1") (pinfunction "1_1") (pintype "passive"))
      (node (ref "U4") (pin "3") (pinfunction "OUT_3") (pintype "bidirectional"))
    )
    (net (code "69") (name "Net-(U7-EN)") (class "Default")
      (node (ref "R16") (pin "1") (pinfunction "1_1") (pintype "passive"))
      (node (ref "U7") (pin "8") (pinfunction "EN_8") (pintype "bidirectional"))
    )
    (net (code "70") (name "VBAT") (class "Default")
      (node (ref "BATT") (pin "2") (pinfunction "2_2") (pintype "passive"))
      (node (ref "C1") (pin "1") (pinfunction "1_1") (pintype "bidirectional"))
      (node (ref "C3") (pin "1") (pinfunction "1_1") (pintype "passive"))
      (node (ref "C4") (pin "2") (pinfunction "2_2") (pintype "passive"))
      (node (ref "R4") (pin "2") (pinfunction "2_2") (pintype "passive"))
      (node (ref "R8") (pin "2") (pinfunction "2_2") (pintype "passive"))
      (node (ref "U2") (pin "6") (pinfunction "IN_6") (pintype "power_in"))
      (node (ref "U3") (pin "3") (pinfunction "VBAT_3") (pintype "power_in"))
      (node (ref "U4") (pin "4") (pinfunction "VIN_4") (pintype "bidirectional"))
    )
    (net (code "71") (name "VBUS") (class "Default")
      (node (ref "CHG") (pin "A") (pinfunction "A_A") (pintype "passive"))
      (node (ref "JP1") (pin "1") (pinfunction "VCC_1") (pintype "bidirectional"))
      (node (ref "U3") (pin "4") (pinfunction "VDD_4") (pintype "power_in"))
    )
    (net (code "72") (name "unconnected-(J2-LVP-Pad6)") (class "Default")
      (node (ref "J2") (pin "6") (pinfunction "LVP_6") (pintype "bidirectional"))
    )
    (net (code "73") (name "unconnected-(JP1-D+-Pad3)") (class "Default")
      (node (ref "JP1") (pin "3") (pinfunction "D+_3") (pintype "bidirectional"))
    )
    (net (code "74") (name "unconnected-(JP1-D--Pad2)") (class "Default")
      (node (ref "JP1") (pin "2") (pinfunction "D-_2") (pintype "bidirectional"))
    )
    (net (code "75") (name "unconnected-(JP1-ID-Pad4)") (class "Default")
      (node (ref "JP1") (pin "4") (pinfunction "ID_4") (pintype "bidirectional"))
    )
    (net (code "76") (name "unconnected-(JTAG-Pad6)") (class "Default")
      (node (ref "JTAG") (pin "6") (pinfunction "6_6") (pintype "passive"))
    )
    (net (code "77") (name "unconnected-(JTAG-Pad8)") (class "Default")
      (node (ref "JTAG") (pin "8") (pinfunction "8_8") (pintype "passive"))
    )
    (net (code "78") (name "unconnected-(P1-PadCSW)") (class "Default")
      (node (ref "P1") (pin "CSW") (pinfunction "CSW_CSW") (pintype "bidirectional"))
    )
    (net (code "79") (name "unconnected-(P1-PadDSW)") (class "Default")
      (node (ref "P1") (pin "DSW") (pinfunction "DSW_DSW") (pintype "bidirectional"))
    )
    (net (code "80") (name "unconnected-(U$35-P8-Pad4)") (class "Default")
      (node (ref "U$35") (pin "4") (pinfunction "P8_4") (pintype "bidirectional"))
    )
    (net (code "81") (name "unconnected-(U$35-P9-Pad5)") (class "Default")
      (node (ref "U$35") (pin "5") (pinfunction "P9_5") (pintype "bidirectional"))
    )
    (net (code "82") (name "unconnected-(U$35-P10-Pad6)") (class "Default")
      (node (ref "U$35") (pin "6") (pinfunction "P10_6") (pintype "bidirectional"))
    )
    (net (code "83") (name "unconnected-(U$35-P17-Pad10)") (class "Default")
      (node (ref "U$35") (pin "10") (pinfunction "P17_10") (pintype "bidirectional"))
    )
    (net (code "84") (name "unconnected-(U$35-P18-Pad11)") (class "Default")
      (node (ref "U$35") (pin "11") (pinfunction "P18_11") (pintype "bidirectional"))
    )
    (net (code "85") (name "unconnected-(U$35-P19-Pad12)") (class "Default")
      (node (ref "U$35") (pin "12") (pinfunction "P19_12") (pintype "bidirectional"))
    )
    (net (code "86") (name "unconnected-(U$35-P23-Pad13)") (class "Default")
      (node (ref "U$35") (pin "13") (pinfunction "P23_13") (pintype "bidirectional"))
    )
    (net (code "87") (name "unconnected-(U$35-P24-Pad14)") (class "Default")
      (node (ref "U$35") (pin "14") (pinfunction "P24_14") (pintype "bidirectional"))
    )
    (net (code "88") (name "unconnected-(U$35-P25-Pad15)") (class "Default")
      (node (ref "U$35") (pin "15") (pinfunction "P25_15") (pintype "bidirectional"))
    )
    (net (code "89") (name "unconnected-(U$35-P26-Pad28)") (class "Default")
      (node (ref "U$35") (pin "28") (pinfunction "P26_28") (pintype "bidirectional"))
    )
    (net (code "90") (name "unconnected-(U$35-P27-Pad27)") (class "Default")
      (node (ref "U$35") (pin "27") (pinfunction "P27_27") (pintype "bidirectional"))
    )
    (net (code "91") (name "unconnected-(U$35-P28-Pad26)") (class "Default")
      (node (ref "U$35") (pin "26") (pinfunction "P28_26") (pintype "bidirectional"))
    )
    (net (code "92") (name "unconnected-(U$35-P29-Pad25)") (class "Default")
      (node (ref "U$35") (pin "25") (pinfunction "P29_25") (pintype "bidirectional"))
    )
    (net (code "93") (name "unconnected-(U$35-P30-Pad24)") (class "Default")
      (node (ref "U$35") (pin "24") (pinfunction "P30_24") (pintype "bidirectional"))
    )
    (net (code "94") (name "unconnected-(U5-NC-Pad3)") (class "Default")
      (node (ref "U5") (pin "3") (pinfunction "NC_3") (pintype "no_connect"))
    )
    (net (code "95") (name "unconnected-(U6-A0-Pad15)") (class "Default")
      (node (ref "U6") (pin "15") (pinfunction "A0_15") (pintype "output"))
    )
    (net (code "96") (name "unconnected-(U6-A1-Pad16)") (class "Default")
      (node (ref "U6") (pin "16") (pinfunction "A1_16") (pintype "bidirectional"))
    )
    (net (code "97") (name "unconnected-(U6-REFN-Pad6)") (class "Default")
      (node (ref "U6") (pin "6") (pinfunction "REFN_6") (pintype "output"))
    )
    (net (code "98") (name "unconnected-(U6-REFP-Pad7)") (class "Default")
      (node (ref "U6") (pin "7") (pinfunction "REFP_7") (pintype "output"))
    )
  )
)
